# IMX_Digital_Interface_Circuit.net
KiCad netlist of a schematic drawn in Altium Designer
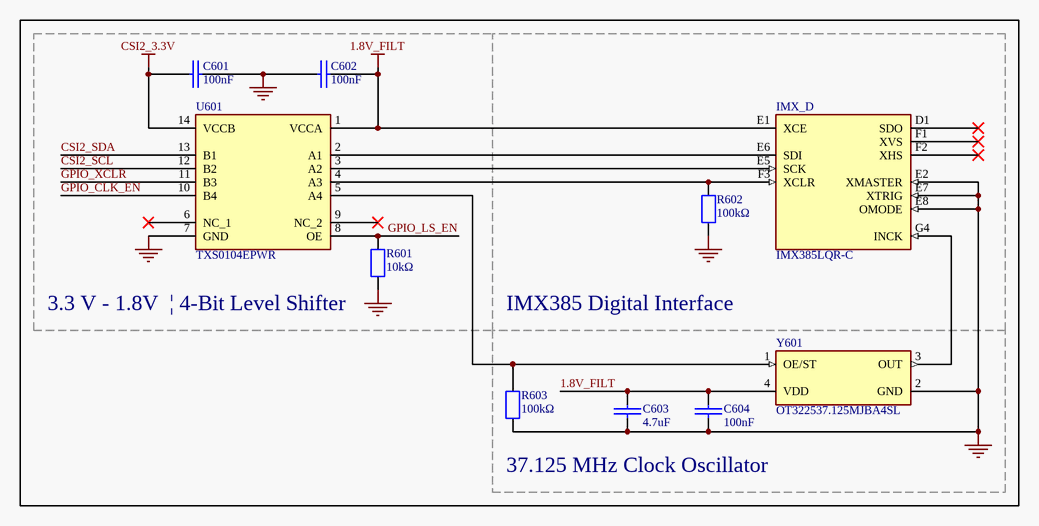
[diagram p0: IMX_Digital Interface Circuit.SchDoc]

(export (version "E")
  (design (tool "Eeschema 10.0.6"))
  (components
    (comp (ref "C601")
      (value "100nF")
      (footprint "Capacitor, 0402")
      (description "Ceramic Capacitor, 16V, 10% +/- Tol, X7R, 0.1uF, SMD, 0402, #CL05B104KO5NNNC, JLC#C1525")
      (libsource (lib "Component Library") (part "Capacitor, 0402, 100nF"))
    )
    (comp (ref "C602")
      (value "100nF")
      (footprint "Capacitor, 0402")
      (description "Ceramic Capacitor, 16V, 10% +/- Tol, X7R, 0.1uF, SMD, 0402, #CL05B104KO5NNNC, JLC#C1525")
      (libsource (lib "Component Library") (part "Capacitor, 0402, 100nF"))
    )
    (comp (ref "C603")
      (value "4.7uF")
      (footprint "Capacitor, 0603")
      (description "Ceramic Capacitor, 10V, 10% +/- Tol, X7R, 4.7uF, SMD, 0603, #GRM188Z71A475KE15D, JLC#C913474")
      (libsource (lib "Component Library") (part "Capacitor, 0603, 4.7uF"))
    )
    (comp (ref "C604")
      (value "100nF")
      (footprint "Capacitor, 0402")
      (description "Ceramic Capacitor, 16V, 10% +/- Tol, X7R, 0.1uF, SMD, 0402, #CL05B104KO5NNNC, JLC#C1525")
      (libsource (lib "Component Library") (part "Capacitor, 0402, 100nF"))
    )
    (comp (ref "IMX_")
      (value "IMX385LQR-C")
      (footprint "IMX385LQR")
      (libsource (lib "Component Library") (part "IMX385LQR"))
    )
    (comp (ref "R601")
      (value "10kΩ")
      (footprint "Resistor, 0603, Yageo")
      (description "Thick Film Resistor, ±1%, ±100ppm/℃, -55℃~+155℃, 0603, 10kΩ, #RC0603FR-0710KL, JLC#C98220")
      (libsource (lib "Component Library") (part "Resistor, 0603, 10kΩ"))
    )
    (comp (ref "R602")
      (value "100kΩ")
      (footprint "Resistor, 0603, Yageo")
      (description "Thick Film Resistor, ±1%, ±100ppm/℃, -55℃~+155℃, 0603, 100kΩ, #RC0603FR-07100KL, JLC#C14675")
      (libsource (lib "Component Library") (part "Resistor, 0603, 100kΩ"))
    )
    (comp (ref "R603")
      (value "100kΩ")
      (footprint "Resistor, 0603, Yageo")
      (description "Thick Film Resistor, ±1%, ±100ppm/℃, -55℃~+155℃, 0603, 100kΩ, #RC0603FR-07100KL, JLC#C14675")
      (libsource (lib "Component Library") (part "Resistor, 0603, 100kΩ"))
    )
    (comp (ref "U601")
      (value "TXS0104EPWR")
      (footprint "Level Shifter, 4-Bit")
      (libsource (lib "Component Library") (part "Level Shifter 4-Bit, Open Drain"))
    )
    (comp (ref "Y601")
      (value "OT322537.125MJBA4SL")
      (footprint "Clock Oscillator, 3235, 37.125")
      (description "1.8V~3.3V ±10ppm ±20ppm CMOS 37.125MHz SMD3225-4P Crystal Oscillators ROHS, JLC#C2831393")
      (libsource (lib "Component Library") (part "Clock Oscillator, SMD3225, 37.125Mhz"))
    )
  )
  (nets
    (net (code "1") (name "/CSI2_SCL") (class "Default")
      (node (ref "U601") (pin "12") (pinfunction "B2_12") (pintype "bidirectional"))
    )
    (net (code "2") (name "/CSI2_SDA") (class "Default")
      (node (ref "U601") (pin "13") (pinfunction "B1_13") (pintype "bidirectional"))
    )
    (net (code "3") (name "/GPIO_CLK_EN") (class "Default")
      (node (ref "U601") (pin "10") (pinfunction "B4_10") (pintype "bidirectional"))
    )
    (net (code "4") (name "/GPIO_LS_EN") (class "Default")
      (node (ref "R601") (pin "2") (pintype "passive"))
      (node (ref "U601") (pin "8") (pinfunction "OE_8") (pintype "passive"))
    )
    (net (code "5") (name "/GPIO_XCLR") (class "Default")
      (node (ref "U601") (pin "11") (pinfunction "B3_11") (pintype "bidirectional"))
    )
    (net (code "6") (name "1.8V_FILT") (class "Default")
      (node (ref "C602") (pin "2") (pinfunction "2_2") (pintype "passive"))
      (node (ref "C603") (pin "1") (pinfunction "1_1") (pintype "passive"))
      (node (ref "C604") (pin "1") (pinfunction "1_1") (pintype "passive"))
      (node (ref "IMX_") (pin "E1") (pinfunction "XCE_E1") (pintype "passive"))
      (node (ref "U601") (pin "1") (pinfunction "VCCA_1") (pintype "passive"))
      (node (ref "Y601") (pin "4") (pinfunction "VDD_4") (pintype "passive"))
    )
    (net (code "7") (name "CSI2_3.3V") (class "Default")
      (node (ref "C601") (pin "2") (pinfunction "2_2") (pintype "passive"))
      (node (ref "U601") (pin "14") (pinfunction "VCCB_14") (pintype "passive"))
    )
    (net (code "8") (name "GND") (class "Default")
      (node (ref "C601") (pin "1") (pinfunction "1_1") (pintype "passive"))
      (node (ref "C602") (pin "1") (pinfunction "1_1") (pintype "passive"))
      (node (ref "C603") (pin "2") (pinfunction "2_2") (pintype "passive"))
      (node (ref "C604") (pin "2") (pinfunction "2_2") (pintype "passive"))
      (node (ref "IMX_") (pin "E2") (pinfunction "XMASTER_E2") (pintype "input"))
      (node (ref "IMX_") (pin "E7") (pinfunction "XTRIG_E7") (pintype "input"))
      (node (ref "IMX_") (pin "E8") (pinfunction "OMODE_E8") (pintype "input"))
      (node (ref "R601") (pin "1") (pintype "passive"))
      (node (ref "R602") (pin "1") (pintype "passive"))
      (node (ref "R603") (pin "1") (pintype "passive"))
      (node (ref "U601") (pin "7") (pinfunction "GND_7") (pintype "passive"))
      (node (ref "Y601") (pin "2") (pinfunction "GND_2") (pintype "passive"))
    )
    (net (code "9") (name "Net-(IMX_D-INCK)") (class "Default")
      (node (ref "IMX_") (pin "G4") (pinfunction "INCK_G4") (pintype "input"))
      (node (ref "Y601") (pin "3") (pinfunction "OUT_3") (pintype "output"))
    )
    (net (code "10") (name "Net-(IMX_D-SCK)") (class "Default")
      (node (ref "IMX_") (pin "E5") (pinfunction "SCK_E5") (pintype "input"))
      (node (ref "U601") (pin "3") (pinfunction "A2_3") (pintype "bidirectional"))
    )
    (net (code "11") (name "Net-(IMX_D-SDI)") (class "Default")
      (node (ref "IMX_") (pin "E6") (pinfunction "SDI_E6") (pintype "bidirectional"))
      (node (ref "U601") (pin "2") (pinfunction "A1_2") (pintype "bidirectional"))
    )
    (net (code "12") (name "Net-(IMX_D-XCLR)") (class "Default")
      (node (ref "IMX_") (pin "F3") (pinfunction "XCLR_F3") (pintype "input"))
      (node (ref "R602") (pin "2") (pintype "passive"))
      (node (ref "U601") (pin "4") (pinfunction "A3_4") (pintype "bidirectional"))
    )
    (net (code "13") (name "Net-(U601-A4)") (class "Default")
      (node (ref "R603") (pin "2") (pintype "passive"))
      (node (ref "U601") (pin "5") (pinfunction "A4_5") (pintype "bidirectional"))
      (node (ref "Y601") (pin "1") (pinfunction "OE/ST_1") (pintype "input"))
    )
    (net (code "14") (name "unconnected-(IMX_D-SDO-PadD1)") (class "Default")
      (node (ref "IMX_") (pin "D1") (pinfunction "SDO_D1") (pintype "passive+no_connect"))
    )
    (net (code "15") (name "unconnected-(IMX_D-XHS-PadF2)") (class "Default")
      (node (ref "IMX_") (pin "F2") (pinfunction "XHS_F2") (pintype "passive+no_connect"))
    )
    (net (code "16") (name "unconnected-(IMX_D-XVS-PadF1)") (class "Default")
      (node (ref "IMX_") (pin "F1") (pinfunction "XVS_F1") (pintype "passive+no_connect"))
    )
    (net (code "17") (name "unconnected-(U601-NC_1-Pad6)") (class "Default")
      (node (ref "U601") (pin "6") (pinfunction "NC_1_6") (pintype "passive+no_connect"))
    )
    (net (code "18") (name "unconnected-(U601-NC_2-Pad9)") (class "Default")
      (node (ref "U601") (pin "9") (pinfunction "NC_2_9") (pintype "passive+no_connect"))
    )
  )
)
